# attiny45-microcontrol-v4_1-small.net
KiCad netlist of a schematic drawn in EAGLE
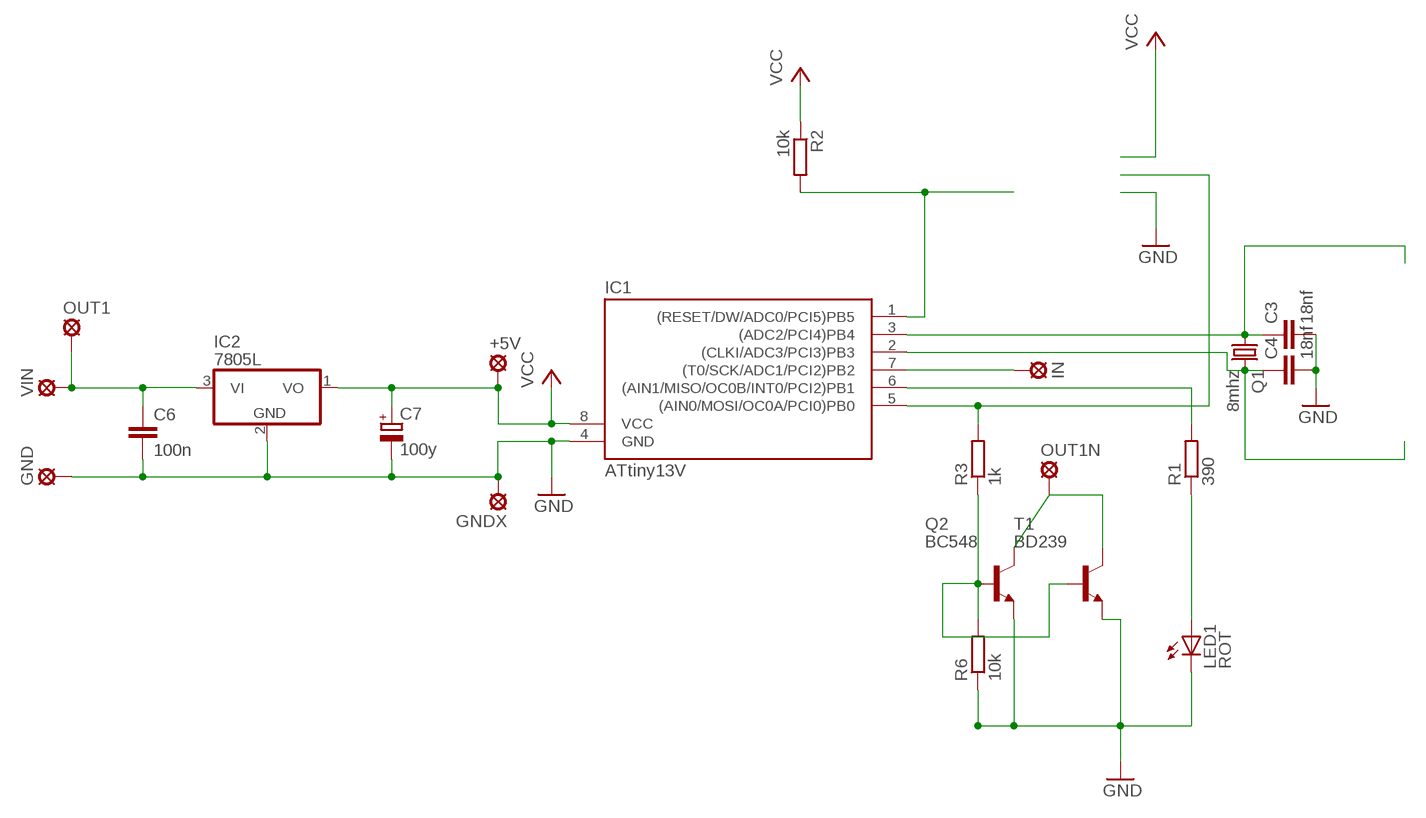
[diagram p0: schematic, sheet 1]

(export (version "E")
  (design (tool "Eeschema 10.0.6"))
  (components
    (comp (ref "+5V")
      (value "LSP10")
      (footprint "eagle-import:LSP10")
      (libsource (lib "eagle-import") (part "LSP10"))
    )
    (comp (ref "C3")
      (value "18nf")
      (footprint "eagle-import:C5B2.5")
      (libsource (lib "eagle-import") (part "C5/2.5"))
    )
    (comp (ref "C4")
      (value "18nf")
      (footprint "eagle-import:C5B2.5")
      (libsource (lib "eagle-import") (part "C5/2.5"))
    )
    (comp (ref "C6")
      (value "100n")
      (footprint "eagle-import:C050-035X075")
      (libsource (lib "eagle-import") (part "C-EU050-035X075"))
    )
    (comp (ref "C7")
      (value "100y")
      (footprint "eagle-import:E2,5-5")
      (libsource (lib "eagle-import") (part "CPOL-EUE2.5-5"))
    )
    (comp (ref "GND")
      (value "LSP10")
      (footprint "eagle-import:LSP10")
      (libsource (lib "eagle-import") (part "LSP10"))
    )
    (comp (ref "GNDX")
      (value "LSP10")
      (footprint "eagle-import:LSP10")
      (libsource (lib "eagle-import") (part "LSP10"))
    )
    (comp (ref "IC1")
      (value "ATtiny13V")
      (footprint "eagle-import:DIL08")
      (libsource (lib "eagle-import") (part "ATTINY13P-20"))
    )
    (comp (ref "IC2")
      (value "7805L")
      (footprint "eagle-import:TO92")
      (libsource (lib "eagle-import") (part "78L05"))
    )
    (comp (ref "IN")
      (value "LSP10")
      (footprint "eagle-import:LSP10")
      (libsource (lib "eagle-import") (part "LSP10"))
    )
    (comp (ref "LED1")
      (value "ROT")
      (footprint "eagle-import:LED3MM")
      (libsource (lib "eagle-import") (part "LED3MM"))
    )
    (comp (ref "OUT1")
      (value "LSP10")
      (footprint "eagle-import:LSP10")
      (libsource (lib "eagle-import") (part "LSP10"))
    )
    (comp (ref "OUT1N")
      (value "LSP10")
      (footprint "eagle-import:LSP10")
      (libsource (lib "eagle-import") (part "LSP10"))
    )
    (comp (ref "Q1")
      (value "8mhz")
      (footprint "eagle-import:HC18U-V")
      (libsource (lib "eagle-import") (part "CRYSTALHC18U-V"))
    )
    (comp (ref "Q2")
      (value "BC548")
      (footprint "eagle-import:TO92-EBC")
      (libsource (lib "eagle-import") (part "BC548"))
    )
    (comp (ref "R1")
      (value "390")
      (footprint "eagle-import:0204_7")
      (libsource (lib "eagle-import") (part "R-EU_0204/7"))
    )
    (comp (ref "R2")
      (value "10k")
      (footprint "eagle-import:R1206")
      (libsource (lib "eagle-import") (part "R-EU_R1206"))
    )
    (comp (ref "R3")
      (value "1k")
      (footprint "eagle-import:0204_7")
      (libsource (lib "eagle-import") (part "R-EU_0204/7"))
    )
    (comp (ref "R6")
      (value "10k")
      (footprint "eagle-import:R1206")
      (libsource (lib "eagle-import") (part "R-EU_R1206"))
    )
    (comp (ref "T1")
      (value "BD239")
      (footprint "eagle-import:TO220")
      (libsource (lib "eagle-import") (part "BD239"))
    )
    (comp (ref "VIN")
      (value "LSP10")
      (footprint "eagle-import:LSP10")
      (libsource (lib "eagle-import") (part "LSP10"))
    )
  )
  (nets
    (net (code "1") (name "GND") (class "Default")
      (node (ref "C3") (pin "2") (pinfunction "2_2") (pintype "passive"))
      (node (ref "C4") (pin "2") (pinfunction "2_2") (pintype "passive"))
      (node (ref "C6") (pin "2") (pinfunction "2_2") (pintype "passive"))
      (node (ref "C7") (pin "-") (pinfunction "-_-") (pintype "passive"))
      (node (ref "GND") (pin "MP") (pinfunction "MP_MP") (pintype "passive"))
      (node (ref "GNDX") (pin "MP") (pinfunction "MP_MP") (pintype "passive"))
      (node (ref "IC1") (pin "4") (pinfunction "GND_4") (pintype "power_in"))
      (node (ref "IC2") (pin "2") (pinfunction "GND_2") (pintype "passive"))
      (node (ref "LED1") (pin "K") (pinfunction "C_K") (pintype "passive"))
      (node (ref "Q2") (pin "E") (pinfunction "E_E") (pintype "passive"))
      (node (ref "R6") (pin "1") (pinfunction "1_1") (pintype "passive"))
      (node (ref "T1") (pin "3") (pinfunction "E_3") (pintype "passive"))
    )
    (net (code "2") (name "Net-(IC1-(ADC2{slash}PCI4)PB4)") (class "Default")
      (node (ref "C3") (pin "1") (pinfunction "1_1") (pintype "passive"))
      (node (ref "IC1") (pin "3") (pinfunction "(ADC2/PCI4)PB4_3") (pintype "bidirectional"))
      (node (ref "Q1") (pin "1") (pinfunction "1_1") (pintype "passive"))
    )
    (net (code "3") (name "Net-(IC1-(AIN0{slash}MOSI{slash}OC0A{slash}PCI0)PB0)") (class "Default")
      (node (ref "IC1") (pin "5") (pinfunction "(AIN0/MOSI/OC0A/PCI0)PB0_5") (pintype "bidirectional"))
      (node (ref "R3") (pin "2") (pinfunction "2_2") (pintype "passive"))
    )
    (net (code "4") (name "Net-(IC1-(AIN1{slash}MISO{slash}OC0B{slash}INT0{slash}PCI2)PB1)") (class "Default")
      (node (ref "IC1") (pin "6") (pinfunction "(AIN1/MISO/OC0B/INT0/PCI2)PB1_6") (pintype "bidirectional"))
      (node (ref "R1") (pin "2") (pinfunction "2_2") (pintype "passive"))
    )
    (net (code "5") (name "Net-(IC1-(CLKI{slash}ADC3{slash}PCI3)PB3)") (class "Default")
      (node (ref "C4") (pin "1") (pinfunction "1_1") (pintype "passive"))
      (node (ref "IC1") (pin "2") (pinfunction "(CLKI/ADC3/PCI3)PB3_2") (pintype "bidirectional"))
      (node (ref "Q1") (pin "2") (pinfunction "2_2") (pintype "passive"))
    )
    (net (code "6") (name "Net-(IC1-(RESET{slash}DW{slash}ADC0{slash}PCI5)PB5)") (class "Default")
      (node (ref "IC1") (pin "1") (pinfunction "(RESET/DW/ADC0/PCI5)PB5_1") (pintype "bidirectional"))
      (node (ref "R2") (pin "2") (pinfunction "2_2") (pintype "passive"))
    )
    (net (code "7") (name "Net-(IC1-(T0{slash}SCK{slash}ADC1{slash}PCI2)PB2)") (class "Default")
      (node (ref "IC1") (pin "7") (pinfunction "(T0/SCK/ADC1/PCI2)PB2_7") (pintype "bidirectional"))
      (node (ref "IN") (pin "MP") (pinfunction "MP_MP") (pintype "passive"))
    )
    (net (code "8") (name "Net-(IC2-VI)") (class "Default")
      (node (ref "C6") (pin "1") (pinfunction "1_1") (pintype "passive"))
      (node (ref "IC2") (pin "3") (pinfunction "VI_3") (pintype "input"))
      (node (ref "OUT1") (pin "MP") (pinfunction "MP_MP") (pintype "passive"))
      (node (ref "VIN") (pin "MP") (pinfunction "MP_MP") (pintype "passive"))
    )
    (net (code "9") (name "Net-(LED1-PadA)") (class "Default")
      (node (ref "LED1") (pin "A") (pinfunction "A_A") (pintype "passive"))
      (node (ref "R1") (pin "1") (pinfunction "1_1") (pintype "passive"))
    )
    (net (code "10") (name "Net-(T1-B)") (class "Default")
      (node (ref "Q2") (pin "B") (pinfunction "B_B") (pintype "passive"))
      (node (ref "R3") (pin "1") (pinfunction "1_1") (pintype "passive"))
      (node (ref "R6") (pin "2") (pinfunction "2_2") (pintype "passive"))
      (node (ref "T1") (pin "1") (pinfunction "B_1") (pintype "passive"))
    )
    (net (code "11") (name "Net-(T1-C)") (class "Default")
      (node (ref "OUT1N") (pin "MP") (pinfunction "MP_MP") (pintype "passive"))
      (node (ref "Q2") (pin "C") (pinfunction "C_C") (pintype "passive"))
      (node (ref "T1") (pin "2") (pinfunction "C_2") (pintype "passive"))
    )
    (net (code "12") (name "VCC") (class "Default")
      (node (ref "+5V") (pin "MP") (pinfunction "MP_MP") (pintype "passive"))
      (node (ref "C7") (pin "+") (pinfunction "+_+") (pintype "passive"))
      (node (ref "IC1") (pin "8") (pinfunction "VCC_8") (pintype "power_in"))
      (node (ref "IC2") (pin "1") (pinfunction "VO_1") (pintype "passive"))
      (node (ref "R2") (pin "1") (pinfunction "1_1") (pintype "passive"))
    )
  )
)
